# QRE1113.net
KiCad netlist of a schematic drawn in Altium Designer
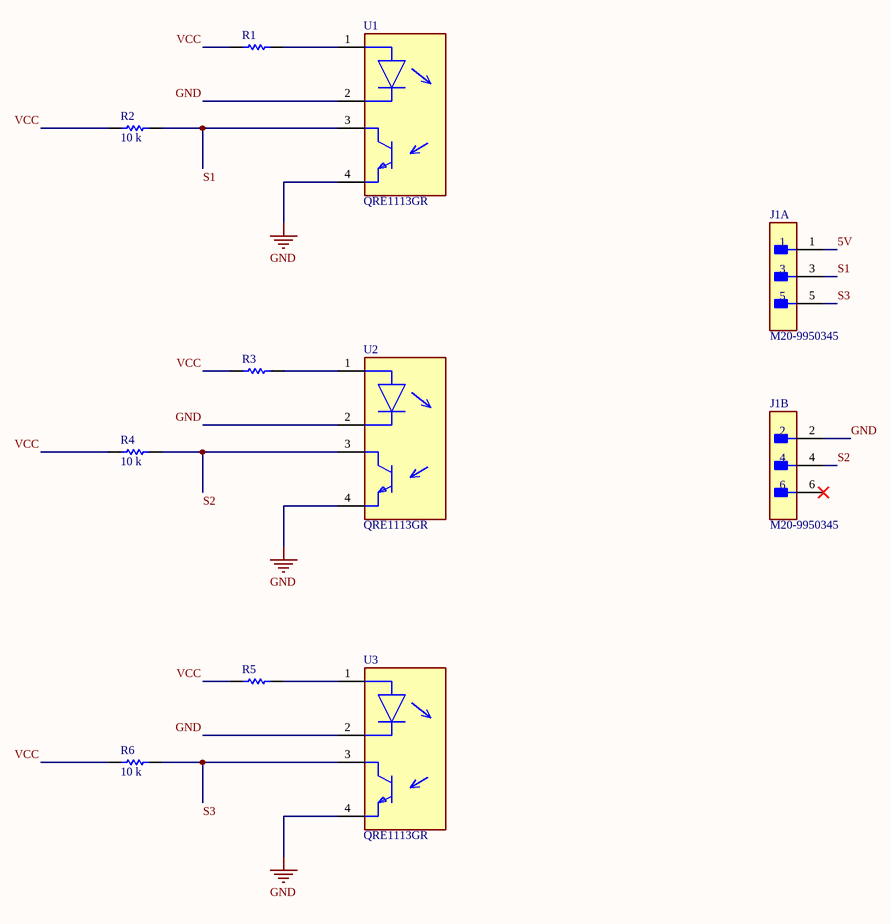
[diagram p0: QRE1113.SchDoc]

(export (version "E")
  (design (tool "Eeschema 10.0.6"))
  (components
    (comp (ref "J1")
      (value "M20-9950345")
      (footprint "FP-M20-9950345-MFG")
      (description "CONN HEADER R/A 6POS 2.54MM")
      (fields
        (field (name "OCTOPART") "https://octopart.com/m20-9950345-harwin-21265213")
        (field (name "MANUFACTURER") "Harwin")
      )
      (libsource (lib "Altium Content Vault") (part "b76336891f9c52daa0497ceff74f613"))
    )
    (comp (ref "R1")
      (value "CRCW0805100RFKEA")
      (footprint "RESC2013X50X30ML20T20")
      (fields (field (name "MANUFACTURER") "Vishay Dale"))
      (libsource (lib "Altium Content Vault") (part "RES"))
    )
    (comp (ref "R2")
      (value "10 k")
      (footprint "RESC2013X60X30ML20T20")
      (fields (field (name "PART NUMBER") "RK73B2ATTD103J") (field (name "MANUFACTURER") "KOA Speer"))
      (libsource (lib "Altium Content Vault") (part "RES"))
    )
    (comp (ref "R3")
      (value "CRCW0805100RFKEA")
      (footprint "RESC2013X50X30ML20T20")
      (fields (field (name "MANUFACTURER") "Vishay Dale"))
      (libsource (lib "Altium Content Vault") (part "RES"))
    )
    (comp (ref "R4")
      (value "10 k")
      (footprint "RESC2013X60X30ML20T20")
      (fields (field (name "PART NUMBER") "RK73B2ATTD103J") (field (name "MANUFACTURER") "KOA Speer"))
      (libsource (lib "Altium Content Vault") (part "RES"))
    )
    (comp (ref "R5")
      (value "CRCW0805100RFKEA")
      (footprint "RESC2013X50X30ML20T20")
      (fields (field (name "MANUFACTURER") "Vishay Dale"))
      (libsource (lib "Altium Content Vault") (part "RES"))
    )
    (comp (ref "R6")
      (value "10 k")
      (footprint "RESC2013X60X30ML20T20")
      (fields (field (name "PART NUMBER") "RK73B2ATTD103J") (field (name "MANUFACTURER") "KOA Speer"))
      (libsource (lib "Altium Content Vault") (part "RES"))
    )
    (comp (ref "U1")
      (value "QRE1113GR")
      (footprint "FP-100CY-MFG")
      (description "SENSOR OPTO TRANS REFL SMD PHOTO")
      (libsource (lib "Altium Content Vault") (part "7f7a55cf1778c7f4ea4f35509e0890d"))
    )
    (comp (ref "U2")
      (value "QRE1113GR")
      (footprint "FP-100CY-MFG")
      (description "SENSOR OPTO TRANS REFL SMD PHOTO")
      (libsource (lib "Altium Content Vault") (part "7f7a55cf1778c7f4ea4f35509e0890d"))
    )
    (comp (ref "U3")
      (value "QRE1113GR")
      (footprint "FP-100CY-MFG")
      (description "SENSOR OPTO TRANS REFL SMD PHOTO")
      (libsource (lib "Altium Content Vault") (part "7f7a55cf1778c7f4ea4f35509e0890d"))
    )
  )
  (nets
    (net (code "1") (name "/5V") (class "Default")
      (node (ref "J1") (pin "1") (pinfunction "1_1") (pintype "passive"))
    )
    (net (code "2") (name "/S1") (class "Default")
      (node (ref "J1") (pin "3") (pinfunction "3_3") (pintype "passive"))
      (node (ref "R2") (pin "2") (pinfunction "2_2") (pintype "passive"))
      (node (ref "U1") (pin "3") (pinfunction "C_3") (pintype "passive"))
    )
    (net (code "3") (name "/S2") (class "Default")
      (node (ref "J1") (pin "4") (pinfunction "4_4") (pintype "passive"))
      (node (ref "R4") (pin "2") (pinfunction "2_2") (pintype "passive"))
      (node (ref "U2") (pin "3") (pinfunction "C_3") (pintype "passive"))
    )
    (net (code "4") (name "/S3") (class "Default")
      (node (ref "J1") (pin "5") (pinfunction "5_5") (pintype "passive"))
      (node (ref "R6") (pin "2") (pinfunction "2_2") (pintype "passive"))
      (node (ref "U3") (pin "3") (pinfunction "C_3") (pintype "passive"))
    )
    (net (code "5") (name "/VCC") (class "Default")
      (node (ref "R1") (pin "1") (pinfunction "1_1") (pintype "passive"))
      (node (ref "R2") (pin "1") (pinfunction "1_1") (pintype "passive"))
      (node (ref "R3") (pin "1") (pinfunction "1_1") (pintype "passive"))
      (node (ref "R4") (pin "1") (pinfunction "1_1") (pintype "passive"))
      (node (ref "R5") (pin "1") (pinfunction "1_1") (pintype "passive"))
      (node (ref "R6") (pin "1") (pinfunction "1_1") (pintype "passive"))
    )
    (net (code "6") (name "GND") (class "Default")
      (node (ref "J1") (pin "2") (pinfunction "2_2") (pintype "passive"))
      (node (ref "U1") (pin "2") (pinfunction "C_2") (pintype "passive"))
      (node (ref "U1") (pin "4") (pinfunction "E_4") (pintype "passive"))
      (node (ref "U2") (pin "2") (pinfunction "C_2") (pintype "passive"))
      (node (ref "U2") (pin "4") (pinfunction "E_4") (pintype "passive"))
      (node (ref "U3") (pin "2") (pinfunction "C_2") (pintype "passive"))
      (node (ref "U3") (pin "4") (pinfunction "E_4") (pintype "passive"))
    )
    (net (code "7") (name "Net-(U1-A)") (class "Default")
      (node (ref "R1") (pin "2") (pinfunction "2_2") (pintype "passive"))
      (node (ref "U1") (pin "1") (pinfunction "A_1") (pintype "passive"))
    )
    (net (code "8") (name "Net-(U2-A)") (class "Default")
      (node (ref "R3") (pin "2") (pinfunction "2_2") (pintype "passive"))
      (node (ref "U2") (pin "1") (pinfunction "A_1") (pintype "passive"))
    )
    (net (code "9") (name "Net-(U3-A)") (class "Default")
      (node (ref "R5") (pin "2") (pinfunction "2_2") (pintype "passive"))
      (node (ref "U3") (pin "1") (pinfunction "A_1") (pintype "passive"))
    )
    (net (code "10") (name "unconnected-(J1-Pad6)") (class "Default")
      (node (ref "J1") (pin "6") (pinfunction "6_6") (pintype "passive+no_connect"))
    )
  )
)
